# atWork_Main.net
KiCad netlist of a schematic drawn in Altium Designer
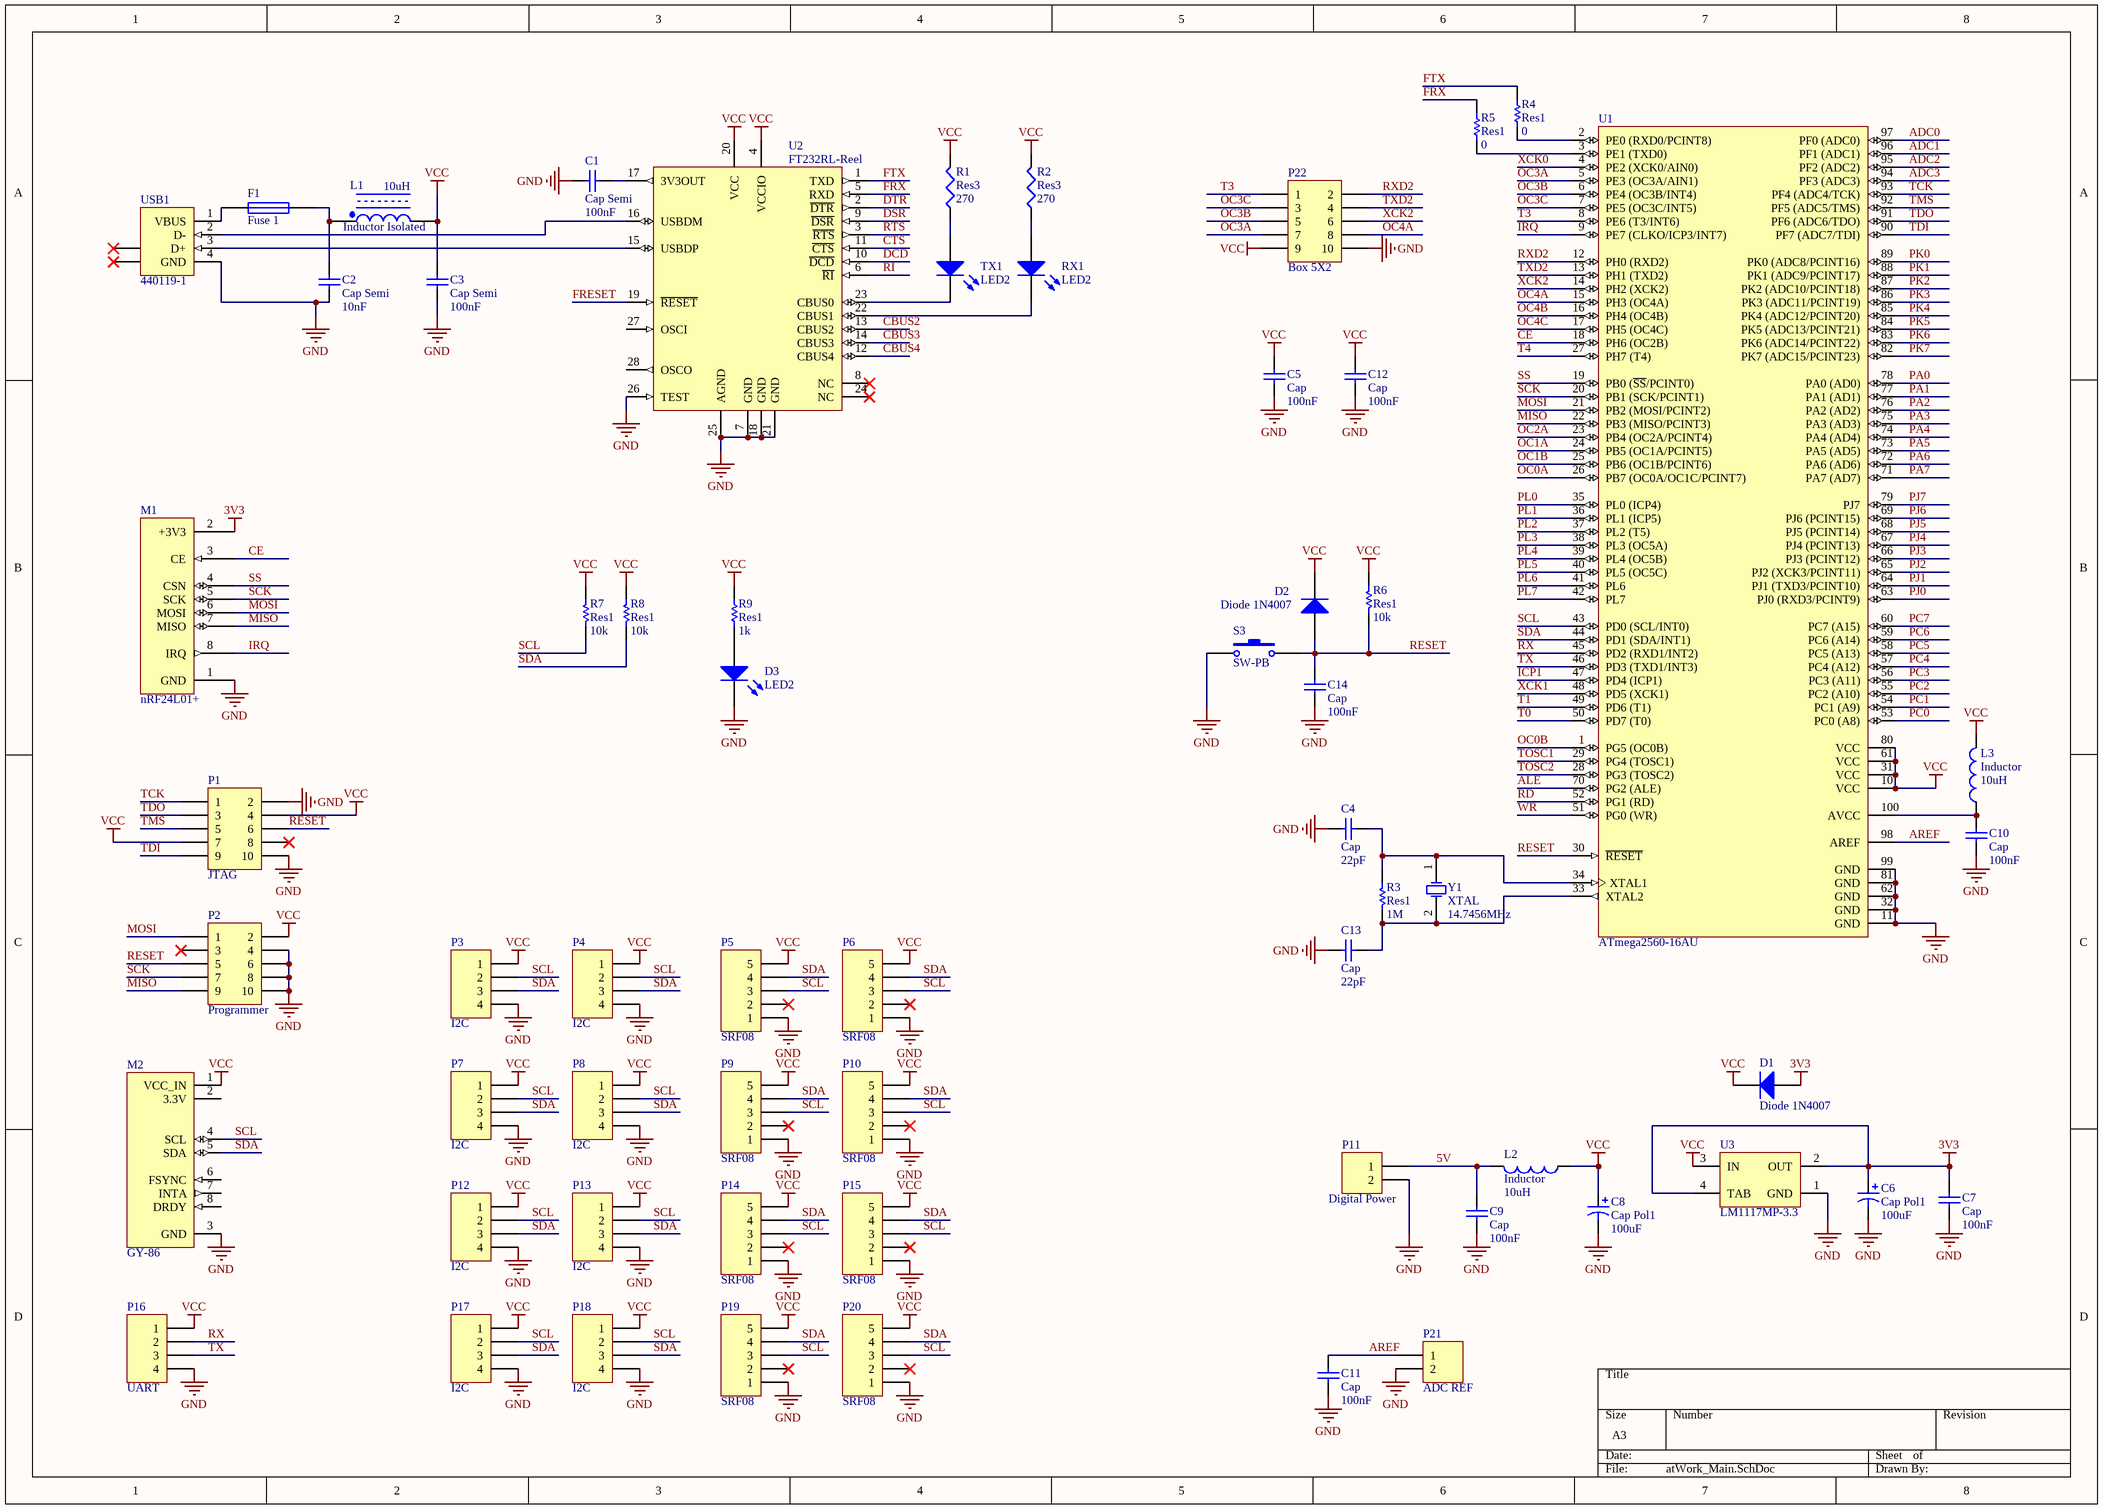
[diagram p0: atWork_Main.SchDoc]

(export (version "E")
  (design (tool "Eeschema 10.0.6"))
  (components
    (comp (ref "C1")
      (value "Cap Semi")
      (footprint "C1206")
      (description "Capacitor (Semiconductor SIM Model)")
      (fields (field (name "ALTIUM_VALUE") "100nF") (field (name "PUBLISHER") "Altium Limited"))
      (libsource (lib "Miscellaneous Devices") (part "Cap Semi"))
    )
    (comp (ref "C2")
      (value "Cap Semi")
      (footprint "C1206")
      (description "Capacitor (Semiconductor SIM Model)")
      (fields (field (name "ALTIUM_VALUE") "10nF") (field (name "PUBLISHER") "Altium Limited"))
      (libsource (lib "Miscellaneous Devices") (part "Cap Semi"))
    )
    (comp (ref "C3")
      (value "Cap Semi")
      (footprint "C1206")
      (description "Capacitor (Semiconductor SIM Model)")
      (fields (field (name "ALTIUM_VALUE") "100nF") (field (name "PUBLISHER") "Altium Limited"))
      (libsource (lib "Miscellaneous Devices") (part "Cap Semi"))
    )
    (comp (ref "C4")
      (value "Cap")
      (footprint "C1206")
      (description "Capacitor")
      (fields (field (name "ALTIUM_VALUE") "22pF") (field (name "PUBLISHER") "Altium Limited"))
      (libsource (lib "Miscellaneous Devices") (part "Cap"))
    )
    (comp (ref "C5")
      (value "Cap")
      (footprint "C1206")
      (description "Capacitor")
      (fields (field (name "ALTIUM_VALUE") "100nF") (field (name "PUBLISHER") "Altium Limited"))
      (libsource (lib "Miscellaneous Devices") (part "Cap"))
    )
    (comp (ref "C6")
      (value "Cap Pol1")
      (footprint "CAP-SMD1")
      (description "Polarized Capacitor (Radial)")
      (fields (field (name "ALTIUM_VALUE") "100uF") (field (name "PUBLISHER") "Altium Limited"))
      (libsource (lib "Miscellaneous Devices") (part "Cap Pol1"))
    )
    (comp (ref "C7")
      (value "Cap")
      (footprint "C1206")
      (description "Capacitor")
      (fields (field (name "ALTIUM_VALUE") "100nF") (field (name "PUBLISHER") "Altium Limited"))
      (libsource (lib "Miscellaneous Devices") (part "Cap"))
    )
    (comp (ref "C8")
      (value "Cap Pol1")
      (footprint "CAP-SMD1")
      (description "Polarized Capacitor (Radial)")
      (fields (field (name "ALTIUM_VALUE") "100uF") (field (name "PUBLISHER") "Altium Limited"))
      (libsource (lib "Miscellaneous Devices") (part "Cap Pol1"))
    )
    (comp (ref "C9")
      (value "Cap")
      (footprint "C1206")
      (description "Capacitor")
      (fields (field (name "ALTIUM_VALUE") "100nF") (field (name "PUBLISHER") "Altium Limited"))
      (libsource (lib "Miscellaneous Devices") (part "Cap"))
    )
    (comp (ref "C10")
      (value "Cap")
      (footprint "C1206")
      (description "Capacitor")
      (fields (field (name "ALTIUM_VALUE") "100nF") (field (name "PUBLISHER") "Altium Limited"))
      (libsource (lib "Miscellaneous Devices") (part "Cap"))
    )
    (comp (ref "C11")
      (value "Cap")
      (footprint "C1206")
      (description "Capacitor")
      (fields (field (name "ALTIUM_VALUE") "100nF") (field (name "PUBLISHER") "Altium Limited"))
      (libsource (lib "Miscellaneous Devices") (part "Cap"))
    )
    (comp (ref "C12")
      (value "Cap")
      (footprint "C1206")
      (description "Capacitor")
      (fields (field (name "ALTIUM_VALUE") "100nF") (field (name "PUBLISHER") "Altium Limited"))
      (libsource (lib "Miscellaneous Devices") (part "Cap"))
    )
    (comp (ref "C13")
      (value "Cap")
      (footprint "C1206")
      (description "Capacitor")
      (fields (field (name "ALTIUM_VALUE") "22pF") (field (name "PUBLISHER") "Altium Limited"))
      (libsource (lib "Miscellaneous Devices") (part "Cap"))
    )
    (comp (ref "C14")
      (value "Cap")
      (footprint "C1206")
      (description "Capacitor")
      (fields (field (name "ALTIUM_VALUE") "100nF") (field (name "PUBLISHER") "Altium Limited"))
      (libsource (lib "Miscellaneous Devices") (part "Cap"))
    )
    (comp (ref "D1")
      (value "Diode 1N4007")
      (footprint "DIODE-SMD")
      (description "1 Amp General Purpose Rectifier")
      (fields (field (name "PUBLISHER") "Altium Limited"))
      (libsource (lib "Miscellaneous Devices") (part "Diode 1N4007"))
    )
    (comp (ref "D2")
      (value "Diode 1N4007")
      (footprint "DIODE-SMD")
      (description "1 Amp General Purpose Rectifier")
      (fields (field (name "PUBLISHER") "Altium Limited"))
      (libsource (lib "Miscellaneous Devices") (part "Diode 1N4007"))
    )
    (comp (ref "D3")
      (value "LED2")
      (footprint "3.2X1.6X1.1")
      (description "Typical RED, GREEN, YELLOW, AMBER GaAs LED")
      (fields (field (name "PUBLISHER") "Altium Limited"))
      (libsource (lib "Miscellaneous Devices") (part "LED2"))
    )
    (comp (ref "F1")
      (value "Fuse 1")
      (footprint "C1206")
      (description "Fuse")
      (fields (field (name "PUBLISHER") "Altium Limited"))
      (libsource (lib "Miscellaneous Devices") (part "Fuse 1"))
    )
    (comp (ref "L1")
      (value "Inductor Isolated")
      (footprint "C1206")
      (description "Isolated Inductor")
      (fields (field (name "ALTIUM_VALUE") "10uH") (field (name "PUBLISHER") "Altium Limited"))
      (libsource (lib "Miscellaneous Devices") (part "Inductor Isolated"))
    )
    (comp (ref "L2")
      (value "Inductor")
      (footprint "C1206")
      (fields (field (name "ALTIUM_VALUE") "10uH") (field (name "PUBLISHER") "Altium Limited"))
      (libsource (lib "") (part "Inductor_1"))
    )
    (comp (ref "L3")
      (value "Inductor")
      (footprint "C1206")
      (fields (field (name "ALTIUM_VALUE") "10uH") (field (name "PUBLISHER") "Altium Limited"))
      (libsource (lib "Miscellaneous Devices") (part "Inductor"))
    )
    (comp (ref "M1")
      (value "nRF24L01+")
      (footprint "NRF24L01+")
      (description "nRF24L01 Single Chip 2.4GHz Tranceiver, +PA +LNA Ver5.1")
      (fields (field (name "DESIGNER") "Meysam Parvizi") (field (name "EMAIL") "meysam.parvizi.ir@gmail.com"))
      (libsource (lib "mp") (part "nRF24L01+"))
    )
    (comp (ref "M2")
      (value "GY-86")
      (footprint "GY-86")
      (description "GY-86 IMU (10DOF MS5611 HMC5883L MPU6050)")
      (fields (field (name "DESIGNER") "Meysam Parvizi") (field (name "EMAIL") "meysam.parvizi.ir@gmail.com"))
      (libsource (lib "mp") (part "GY-86"))
    )
    (comp (ref "P1")
      (value "JTAG")
      (footprint "BOX2X5")
      (description "Box, 5-Pin, Dual row")
      (fields (field (name "DESIGNER") "Meysam Parvizi") (field (name "EMAIL") "meysam.parvizi.ir@gmail.com"))
      (libsource (lib "mp") (part "Box 5X2"))
    )
    (comp (ref "P2")
      (value "Programmer")
      (footprint "BOX2X5")
      (description "Box, 5-Pin, Dual row")
      (fields (field (name "DESIGNER") "Meysam Parvizi") (field (name "EMAIL") "meysam.parvizi.ir@gmail.com"))
      (libsource (lib "mp") (part "Box 5X2"))
    )
    (comp (ref "P3")
      (value "I2C")
      (footprint "XH4PIN")
      (description "Header, 4-Pin")
      (fields (field (name "PUBLISHER") "Altium Limited"))
      (libsource (lib "Miscellaneous Connectors") (part "Header 4"))
    )
    (comp (ref "P4")
      (value "I2C")
      (footprint "XH4PIN")
      (description "Header, 4-Pin")
      (fields (field (name "PUBLISHER") "Altium Limited"))
      (libsource (lib "Miscellaneous Connectors") (part "Header 4"))
    )
    (comp (ref "P5")
      (value "SRF08")
      (footprint "XH5PIN")
      (fields (field (name "PUBLISHER") "Altium Limited"))
      (libsource (lib "Miscellaneous Connectors") (part "Header 5"))
    )
    (comp (ref "P6")
      (value "SRF08")
      (footprint "XH5PIN")
      (fields (field (name "PUBLISHER") "Altium Limited"))
      (libsource (lib "Miscellaneous Connectors") (part "Header 5"))
    )
    (comp (ref "P7")
      (value "I2C")
      (footprint "XH4PIN")
      (description "Header, 4-Pin")
      (fields (field (name "PUBLISHER") "Altium Limited"))
      (libsource (lib "Miscellaneous Connectors") (part "Header 4"))
    )
    (comp (ref "P8")
      (value "I2C")
      (footprint "XH4PIN")
      (description "Header, 4-Pin")
      (fields (field (name "PUBLISHER") "Altium Limited"))
      (libsource (lib "Miscellaneous Connectors") (part "Header 4"))
    )
    (comp (ref "P9")
      (value "SRF08")
      (footprint "XH5PIN")
      (fields (field (name "PUBLISHER") "Altium Limited"))
      (libsource (lib "Miscellaneous Connectors") (part "Header 5"))
    )
    (comp (ref "P10")
      (value "SRF08")
      (footprint "XH5PIN")
      (fields (field (name "PUBLISHER") "Altium Limited"))
      (libsource (lib "Miscellaneous Connectors") (part "Header 5"))
    )
    (comp (ref "P11")
      (value "Digital Power")
      (footprint "XH2PIN")
      (description "Header, 2-Pin")
      (fields (field (name "PUBLISHER") "Altium Limited"))
      (libsource (lib "Miscellaneous Connectors") (part "Header 2"))
    )
    (comp (ref "P12")
      (value "I2C")
      (footprint "XH4PIN")
      (description "Header, 4-Pin")
      (fields (field (name "PUBLISHER") "Altium Limited"))
      (libsource (lib "Miscellaneous Connectors") (part "Header 4"))
    )
    (comp (ref "P13")
      (value "I2C")
      (footprint "XH4PIN")
      (description "Header, 4-Pin")
      (fields (field (name "PUBLISHER") "Altium Limited"))
      (libsource (lib "Miscellaneous Connectors") (part "Header 4"))
    )
    (comp (ref "P14")
      (value "SRF08")
      (footprint "XH5PIN")
      (fields (field (name "PUBLISHER") "Altium Limited"))
      (libsource (lib "Miscellaneous Connectors") (part "Header 5"))
    )
    (comp (ref "P15")
      (value "SRF08")
      (footprint "XH5PIN")
      (fields (field (name "PUBLISHER") "Altium Limited"))
      (libsource (lib "Miscellaneous Connectors") (part "Header 5"))
    )
    (comp (ref "P16")
      (value "UART")
      (footprint "XH4PIN")
      (description "Header, 4-Pin")
      (fields (field (name "PUBLISHER") "Altium Limited"))
      (libsource (lib "Miscellaneous Connectors") (part "Header 4"))
    )
    (comp (ref "P17")
      (value "I2C")
      (footprint "XH4PIN")
      (description "Header, 4-Pin")
      (fields (field (name "PUBLISHER") "Altium Limited"))
      (libsource (lib "Miscellaneous Connectors") (part "Header 4"))
    )
    (comp (ref "P18")
      (value "I2C")
      (footprint "XH4PIN")
      (description "Header, 4-Pin")
      (fields (field (name "PUBLISHER") "Altium Limited"))
      (libsource (lib "Miscellaneous Connectors") (part "Header 4"))
    )
    (comp (ref "P19")
      (value "SRF08")
      (footprint "XH5PIN")
      (fields (field (name "PUBLISHER") "Altium Limited"))
      (libsource (lib "Miscellaneous Connectors") (part "Header 5"))
    )
    (comp (ref "P20")
      (value "SRF08")
      (footprint "XH5PIN")
      (fields (field (name "PUBLISHER") "Altium Limited"))
      (libsource (lib "Miscellaneous Connectors") (part "Header 5"))
    )
    (comp (ref "P21")
      (value "ADC REF")
      (footprint "XH2PIN")
      (description "Header, 2-Pin")
      (fields (field (name "PUBLISHER") "Altium Limited"))
      (libsource (lib "") (part "Header 2_1"))
    )
    (comp (ref "P22")
      (value "Box 5X2")
      (footprint "BOX2X5")
      (description "Box, 5-Pin, Dual row")
      (fields (field (name "DESIGNER") "Meysam Parvizi") (field (name "EMAIL") "meysam.parvizi.ir@gmail.com"))
      (libsource (lib "mp") (part "Box 5X2"))
    )
    (comp (ref "R1")
      (value "Res3")
      (footprint "C1206")
      (description "Resistor")
      (fields (field (name "ALTIUM_VALUE") "270") (field (name "PUBLISHER") "Altium Limited"))
      (libsource (lib "Miscellaneous Devices") (part "Res3"))
    )
    (comp (ref "R2")
      (value "Res3")
      (footprint "C1206")
      (description "Resistor")
      (fields (field (name "ALTIUM_VALUE") "270") (field (name "PUBLISHER") "Altium Limited"))
      (libsource (lib "Miscellaneous Devices") (part "Res3"))
    )
    (comp (ref "R3")
      (value "Res1")
      (footprint "C1206")
      (description "Resistor")
      (fields (field (name "ALTIUM_VALUE") "1M") (field (name "PUBLISHER") "Altium Limited"))
      (libsource (lib "Miscellaneous Devices") (part "Res1"))
    )
    (comp (ref "R4")
      (value "Res1")
      (footprint "C1206")
      (description "Resistor")
      (fields (field (name "ALTIUM_VALUE") "0") (field (name "PUBLISHER") "Altium Limited"))
      (libsource (lib "Miscellaneous Devices") (part "Res1"))
    )
    (comp (ref "R5")
      (value "Res1")
      (footprint "C1206")
      (description "Resistor")
      (fields (field (name "ALTIUM_VALUE") "0") (field (name "PUBLISHER") "Altium Limited"))
      (libsource (lib "Miscellaneous Devices") (part "Res1"))
    )
    (comp (ref "R6")
      (value "Res1")
      (footprint "C1206")
      (description "Resistor")
      (fields (field (name "ALTIUM_VALUE") "10k") (field (name "PUBLISHER") "Altium Limited"))
      (libsource (lib "Miscellaneous Devices") (part "Res1"))
    )
    (comp (ref "R7")
      (value "Res1")
      (footprint "C1206")
      (description "Resistor")
      (fields (field (name "ALTIUM_VALUE") "10k") (field (name "PUBLISHER") "Altium Limited"))
      (libsource (lib "Miscellaneous Devices") (part "Res1"))
    )
    (comp (ref "R8")
      (value "Res1")
      (footprint "C1206")
      (description "Resistor")
      (fields (field (name "ALTIUM_VALUE") "10k") (field (name "PUBLISHER") "Altium Limited"))
      (libsource (lib "Miscellaneous Devices") (part "Res1"))
    )
    (comp (ref "R9")
      (value "Res1")
      (footprint "C1206")
      (description "Resistor")
      (fields (field (name "ALTIUM_VALUE") "1k") (field (name "PUBLISHER") "Altium Limited"))
      (libsource (lib "Miscellaneous Devices") (part "Res1"))
    )
    (comp (ref "RX1")
      (value "LED2")
      (footprint "3.2X1.6X1.1")
      (description "Typical RED, GREEN, YELLOW, AMBER GaAs LED")
      (fields (field (name "PUBLISHER") "Altium Limited"))
      (libsource (lib "Miscellaneous Devices") (part "LED2"))
    )
    (comp (ref "S3")
      (value "SW-PB")
      (footprint "PUSH1")
      (description "Switch")
      (fields (field (name "PUBLISHER") "Altium Limited"))
      (libsource (lib "Miscellaneous Devices") (part "SW-PB"))
    )
    (comp (ref "TX1")
      (value "LED2")
      (footprint "3.2X1.6X1.1")
      (description "Typical RED, GREEN, YELLOW, AMBER GaAs LED")
      (fields (field (name "PUBLISHER") "Altium Limited"))
      (libsource (lib "Miscellaneous Devices") (part "LED2"))
    )
    (comp (ref "U1")
      (value "ATmega2560-16AU")
      (footprint "100A_M")
      (fields (field (name "PUBLISHER") "Altium Limited"))
      (libsource (lib "Atmel Microcontroller 8-Bit megaAVR") (part "ATmega2560-16AU"))
    )
    (comp (ref "U2")
      (value "FT232RL-Reel")
      (footprint "SSOP-28_M")
      (description "USB UART Asynchronous Serial Data Transfer Chip, 28-pin SSOP, Tape and Reel")
      (fields (field (name "MANUFACTURER") "FTDI"))
      (libsource (lib "FTDI FT Series") (part "FT232RL-Reel"))
    )
    (comp (ref "U3")
      (value "LM1117MP-3.3")
      (footprint "MP04A_M")
      (description "800mA Low-Dropout Linear Regulator, 4-pin SOT-223")
      (fields
        (field (name "MANUFACTURER") "National Semiconductor")
        (field (name "PUBLISHER") "Altium Limited")
      )
      (libsource (lib "NSC LDO") (part "LM1117MP-3.3"))
    )
    (comp (ref "USB1")
      (value "440119-1")
      (footprint "mp:USB-B")
      (description "USB 1.1, Right Angle, Thru-Hole, B Type, Receptacle, 4 Position, Beige")
      (fields (field (name "PUBLISHER") "Altium Limited"))
      (libsource (lib "AMP Serial Bus USB") (part "440119-1"))
    )
    (comp (ref "Y1")
      (value "XTAL")
      (footprint "XTAL")
      (description "Crystal Oscillator")
      (fields
        (field (name "ALTIUM_VALUE") "14.7456MHz")
        (field (name "DESIGNER") "Meysam Parvizi")
        (field (name "EMAIL") "meysam.parvizi.ir@gmail.com")
      )
      (libsource (lib "mp") (part "XTAL"))
    )
  )
  (nets
    (net (code "1") (name "/5V") (class "Default")
      (node (ref "C9") (pin "2") (pinfunction "2_2") (pintype "passive"))
      (node (ref "L2") (pin "1") (pinfunction "1_1") (pintype "passive"))
      (node (ref "P11") (pin "1") (pinfunction "1_1") (pintype "passive"))
    )
    (net (code "2") (name "/ADC0") (class "Default")
      (node (ref "U1") (pin "97") (pinfunction "PF0_(ADC0)_97") (pintype "bidirectional"))
    )
    (net (code "3") (name "/ADC1") (class "Default")
      (node (ref "U1") (pin "96") (pinfunction "PF1_(ADC1)_96") (pintype "bidirectional"))
    )
    (net (code "4") (name "/ADC2") (class "Default")
      (node (ref "U1") (pin "95") (pinfunction "PF2_(ADC2)_95") (pintype "bidirectional"))
    )
    (net (code "5") (name "/ADC3") (class "Default")
      (node (ref "U1") (pin "94") (pinfunction "PF3_(ADC3)_94") (pintype "bidirectional"))
    )
    (net (code "6") (name "/ALE") (class "Default")
      (node (ref "U1") (pin "70") (pinfunction "PG2_(ALE)_70") (pintype "bidirectional"))
    )
    (net (code "7") (name "/AREF") (class "Default")
      (node (ref "C11") (pin "2") (pinfunction "2_2") (pintype "passive"))
      (node (ref "P21") (pin "1") (pinfunction "1_1") (pintype "passive"))
      (node (ref "U1") (pin "98") (pinfunction "AREF_98") (pintype "power_in"))
    )
    (net (code "8") (name "/CBUS2") (class "Default")
      (node (ref "U2") (pin "13") (pinfunction "CBUS2_13") (pintype "bidirectional"))
    )
    (net (code "9") (name "/CBUS3") (class "Default")
      (node (ref "U2") (pin "14") (pinfunction "CBUS3_14") (pintype "bidirectional"))
    )
    (net (code "10") (name "/CBUS4") (class "Default")
      (node (ref "U2") (pin "12") (pinfunction "CBUS4_12") (pintype "bidirectional"))
    )
    (net (code "11") (name "/CE") (class "Default")
      (node (ref "M1") (pin "3") (pinfunction "CE_3") (pintype "input"))
      (node (ref "U1") (pin "18") (pinfunction "PH6_(OC2B)_18") (pintype "bidirectional"))
    )
    (net (code "12") (name "/CTS") (class "Default")
      (node (ref "U2") (pin "11") (pinfunction "~{CTS}_11") (pintype "input"))
    )
    (net (code "13") (name "/DCD") (class "Default")
      (node (ref "U2") (pin "10") (pinfunction "~{DCD}_10") (pintype "input"))
    )
    (net (code "14") (name "/DSR") (class "Default")
      (node (ref "U2") (pin "9") (pinfunction "~{DSR}_9") (pintype "input"))
    )
    (net (code "15") (name "/DTR") (class "Default")
      (node (ref "U2") (pin "2") (pinfunction "~{DTR}_2") (pintype "output"))
    )
    (net (code "16") (name "/FRESET") (class "Default")
      (node (ref "U2") (pin "19") (pinfunction "~{RESET}_19") (pintype "input"))
    )
    (net (code "17") (name "/FRX") (class "Default")
      (node (ref "R5") (pin "2") (pinfunction "2_2") (pintype "passive"))
      (node (ref "U2") (pin "5") (pinfunction "RXD_5") (pintype "input"))
    )
    (net (code "18") (name "/FTX") (class "Default")
      (node (ref "R4") (pin "1") (pinfunction "1_1") (pintype "passive"))
      (node (ref "U2") (pin "1") (pinfunction "TXD_1") (pintype "output"))
    )
    (net (code "19") (name "/ICP1") (class "Default")
      (node (ref "U1") (pin "47") (pinfunction "PD4_(ICP1)_47") (pintype "bidirectional"))
    )
    (net (code "20") (name "/IRQ") (class "Default")
      (node (ref "M1") (pin "8") (pinfunction "IRQ_8") (pintype "output"))
      (node (ref "U1") (pin "9") (pinfunction "PE7_(CLKO/ICP3/INT7)_9") (pintype "bidirectional"))
    )
    (net (code "21") (name "/MISO") (class "Default")
      (node (ref "M1") (pin "7") (pinfunction "MISO_7") (pintype "bidirectional"))
      (node (ref "P2") (pin "9") (pinfunction "9_9") (pintype "passive"))
      (node (ref "U1") (pin "22") (pinfunction "PB3_(MISO/PCINT3)_22") (pintype "bidirectional"))
    )
    (net (code "22") (name "/MOSI") (class "Default")
      (node (ref "M1") (pin "6") (pinfunction "MOSI_6") (pintype "bidirectional"))
      (node (ref "P2") (pin "1") (pinfunction "1_1") (pintype "passive"))
      (node (ref "U1") (pin "21") (pinfunction "PB2_(MOSI/PCINT2)_21") (pintype "bidirectional"))
    )
    (net (code "23") (name "/OC0A") (class "Default")
      (node (ref "U1") (pin "26") (pinfunction "PB7_(OC0A/OC1C/PCINT7)_26") (pintype "bidirectional"))
    )
    (net (code "24") (name "/OC0B") (class "Default")
      (node (ref "U1") (pin "1") (pinfunction "PG5_(OC0B)_1") (pintype "bidirectional"))
    )
    (net (code "25") (name "/OC1A") (class "Default")
      (node (ref "U1") (pin "24") (pinfunction "PB5_(OC1A/PCINT5)_24") (pintype "bidirectional"))
    )
    (net (code "26") (name "/OC1B") (class "Default")
      (node (ref "U1") (pin "25") (pinfunction "PB6_(OC1B/PCINT6)_25") (pintype "bidirectional"))
    )
    (net (code "27") (name "/OC2A") (class "Default")
      (node (ref "U1") (pin "23") (pinfunction "PB4_(OC2A/PCINT4)_23") (pintype "bidirectional"))
    )
    (net (code "28") (name "/OC3A") (class "Default")
      (node (ref "P22") (pin "7") (pinfunction "7_7") (pintype "passive"))
      (node (ref "U1") (pin "5") (pinfunction "PE3_(OC3A/AIN1)_5") (pintype "bidirectional"))
    )
    (net (code "29") (name "/OC3B") (class "Default")
      (node (ref "P22") (pin "5") (pinfunction "5_5") (pintype "passive"))
      (node (ref "U1") (pin "6") (pinfunction "PE4_(OC3B/INT4)_6") (pintype "bidirectional"))
    )
    (net (code "30") (name "/OC3C") (class "Default")
      (node (ref "P22") (pin "3") (pinfunction "3_3") (pintype "passive"))
      (node (ref "U1") (pin "7") (pinfunction "PE5_(OC3C/INT5)_7") (pintype "bidirectional"))
    )
    (net (code "31") (name "/OC4A") (class "Default")
      (node (ref "P22") (pin "8") (pinfunction "8_8") (pintype "passive"))
      (node (ref "U1") (pin "15") (pinfunction "PH3_(OC4A)_15") (pintype "bidirectional"))
    )
    (net (code "32") (name "/OC4B") (class "Default")
      (node (ref "U1") (pin "16") (pinfunction "PH4_(OC4B)_16") (pintype "bidirectional"))
    )
    (net (code "33") (name "/OC4C") (class "Default")
      (node (ref "U1") (pin "17") (pinfunction "PH5_(OC4C)_17") (pintype "bidirectional"))
    )
    (net (code "34") (name "/PA0") (class "Default")
      (node (ref "U1") (pin "78") (pinfunction "PA0_(AD0)_78") (pintype "bidirectional"))
    )
    (net (code "35") (name "/PA1") (class "Default")
      (node (ref "U1") (pin "77") (pinfunction "PA1_(AD1)_77") (pintype "bidirectional"))
    )
    (net (code "36") (name "/PA2") (class "Default")
      (node (ref "U1") (pin "76") (pinfunction "PA2_(AD2)_76") (pintype "bidirectional"))
    )
    (net (code "37") (name "/PA3") (class "Default")
      (node (ref "U1") (pin "75") (pinfunction "PA3_(AD3)_75") (pintype "bidirectional"))
    )
    (net (code "38") (name "/PA4") (class "Default")
      (node (ref "U1") (pin "74") (pinfunction "PA4_(AD4)_74") (pintype "bidirectional"))
    )
    (net (code "39") (name "/PA5") (class "Default")
      (node (ref "U1") (pin "73") (pinfunction "PA5_(AD5)_73") (pintype "bidirectional"))
    )
    (net (code "40") (name "/PA6") (class "Default")
      (node (ref "U1") (pin "72") (pinfunction "PA6_(AD6)_72") (pintype "bidirectional"))
    )
    (net (code "41") (name "/PA7") (class "Default")
      (node (ref "U1") (pin "71") (pinfunction "PA7_(AD7)_71") (pintype "bidirectional"))
    )
    (net (code "42") (name "/PC0") (class "Default")
      (node (ref "U1") (pin "53") (pinfunction "PC0_(A8)_53") (pintype "bidirectional"))
    )
    (net (code "43") (name "/PC1") (class "Default")
      (node (ref "U1") (pin "54") (pinfunction "PC1_(A9)_54") (pintype "bidirectional"))
    )
    (net (code "44") (name "/PC2") (class "Default")
      (node (ref "U1") (pin "55") (pinfunction "PC2_(A10)_55") (pintype "bidirectional"))
    )
    (net (code "45") (name "/PC3") (class "Default")
      (node (ref "U1") (pin "56") (pinfunction "PC3_(A11)_56") (pintype "bidirectional"))
    )
    (net (code "46") (name "/PC4") (class "Default")
      (node (ref "U1") (pin "57") (pinfunction "PC4_(A12)_57") (pintype "bidirectional"))
    )
    (net (code "47") (name "/PC5") (class "Default")
      (node (ref "U1") (pin "58") (pinfunction "PC5_(A13)_58") (pintype "bidirectional"))
    )
    (net (code "48") (name "/PC6") (class "Default")
      (node (ref "U1") (pin "59") (pinfunction "PC6_(A14)_59") (pintype "bidirectional"))
    )
    (net (code "49") (name "/PC7") (class "Default")
      (node (ref "U1") (pin "60") (pinfunction "PC7_(A15)_60") (pintype "bidirectional"))
    )
    (net (code "50") (name "/PJ0") (class "Default")
      (node (ref "U1") (pin "63") (pinfunction "PJ0_(RXD3/PCINT9)_63") (pintype "bidirectional"))
    )
    (net (code "51") (name "/PJ1") (class "Default")
      (node (ref "U1") (pin "64") (pinfunction "PJ1_(TXD3/PCINT10)_64") (pintype "bidirectional"))
    )
    (net (code "52") (name "/PJ2") (class "Default")
      (node (ref "U1") (pin "65") (pinfunction "PJ2_(XCK3/PCINT11)_65") (pintype "bidirectional"))
    )
    (net (code "53") (name "/PJ3") (class "Default")
      (node (ref "U1") (pin "66") (pinfunction "PJ3_(PCINT12)_66") (pintype "bidirectional"))
    )
    (net (code "54") (name "/PJ4") (class "Default")
      (node (ref "U1") (pin "67") (pinfunction "PJ4_(PCINT13)_67") (pintype "bidirectional"))
    )
    (net (code "55") (name "/PJ5") (class "Default")
      (node (ref "U1") (pin "68") (pinfunction "PJ5_(PCINT14)_68") (pintype "bidirectional"))
    )
    (net (code "56") (name "/PJ6") (class "Default")
      (node (ref "U1") (pin "69") (pinfunction "PJ6_(PCINT15)_69") (pintype "bidirectional"))
    )
    (net (code "57") (name "/PJ7") (class "Default")
      (node (ref "U1") (pin "79") (pinfunction "PJ7_79") (pintype "bidirectional"))
    )
    (net (code "58") (name "/PK0") (class "Default")
      (node (ref "U1") (pin "89") (pinfunction "PK0_(ADC8/PCINT16)_89") (pintype "bidirectional"))
    )
    (net (code "59") (name "/PK1") (class "Default")
      (node (ref "U1") (pin "88") (pinfunction "PK1_(ADC9/PCINT17)_88") (pintype "bidirectional"))
    )
    (net (code "60") (name "/PK2") (class "Default")
      (node (ref "U1") (pin "87") (pinfunction "PK2_(ADC10/PCINT18)_87") (pintype "bidirectional"))
    )
    (net (code "61") (name "/PK3") (class "Default")
      (node (ref "U1") (pin "86") (pinfunction "PK3_(ADC11/PCINT19)_86") (pintype "bidirectional"))
    )
    (net (code "62") (name "/PK4") (class "Default")
      (node (ref "U1") (pin "85") (pinfunction "PK4_(ADC12/PCINT20)_85") (pintype "bidirectional"))
    )
    (net (code "63") (name "/PK5") (class "Default")
      (node (ref "U1") (pin "84") (pinfunction "PK5_(ADC13/PCINT21)_84") (pintype "bidirectional"))
    )
    (net (code "64") (name "/PK6") (class "Default")
      (node (ref "U1") (pin "83") (pinfunction "PK6_(ADC14/PCINT22)_83") (pintype "bidirectional"))
    )
    (net (code "65") (name "/PK7") (class "Default")
      (node (ref "U1") (pin "82") (pinfunction "PK7_(ADC15/PCINT23)_82") (pintype "bidirectional"))
    )
    (net (code "66") (name "/PL0") (class "Default")
      (node (ref "U1") (pin "35") (pinfunction "PL0_(ICP4)_35") (pintype "bidirectional"))
    )
    (net (code "67") (name "/PL1") (class "Default")
      (node (ref "U1") (pin "36") (pinfunction "PL1_(ICP5)_36") (pintype "bidirectional"))
    )
    (net (code "68") (name "/PL2") (class "Default")
      (node (ref "U1") (pin "37") (pinfunction "PL2_(T5)_37") (pintype "bidirectional"))
    )
    (net (code "69") (name "/PL3") (class "Default")
      (node (ref "U1") (pin "38") (pinfunction "PL3_(OC5A)_38") (pintype "bidirectional"))
    )
    (net (code "70") (name "/PL4") (class "Default")
      (node (ref "U1") (pin "39") (pinfunction "PL4_(OC5B)_39") (pintype "bidirectional"))
    )
    (net (code "71") (name "/PL5") (class "Default")
      (node (ref "U1") (pin "40") (pinfunction "PL5_(OC5C)_40") (pintype "bidirectional"))
    )
    (net (code "72") (name "/PL6") (class "Default")
      (node (ref "U1") (pin "41") (pinfunction "PL6_41") (pintype "bidirectional"))
    )
    (net (code "73") (name "/PL7") (class "Default")
      (node (ref "U1") (pin "42") (pinfunction "PL7_42") (pintype "bidirectional"))
    )
    (net (code "74") (name "/RD") (class "Default")
      (node (ref "U1") (pin "52") (pinfunction "PG1_(RD)_52") (pintype "bidirectional"))
    )
    (net (code "75") (name "/RESET") (class "Default")
      (node (ref "C14") (pin "2") (pinfunction "2_2") (pintype "passive"))
      (node (ref "D2") (pin "1") (pinfunction "A_1") (pintype "passive"))
      (node (ref "P1") (pin "6") (pinfunction "6_6") (pintype "passive"))
      (node (ref "P2") (pin "5") (pinfunction "5_5") (pintype "passive"))
      (node (ref "R6") (pin "2") (pinfunction "2_2") (pintype "passive"))
      (node (ref "S3") (pin "1") (pinfunction "1_1") (pintype "passive"))
      (node (ref "U1") (pin "30") (pinfunction "~{RESET}_30") (pintype "input"))
    )
    (net (code "76") (name "/RI") (class "Default")
      (node (ref "U2") (pin "6") (pinfunction "~{RI}_6") (pintype "input"))
    )
    (net (code "77") (name "/RTS") (class "Default")
      (node (ref "U2") (pin "3") (pinfunction "~{RTS}_3") (pintype "output"))
    )
    (net (code "78") (name "/RX") (class "Default")
      (node (ref "P16") (pin "2") (pinfunction "2_2") (pintype "passive"))
      (node (ref "U1") (pin "45") (pinfunction "PD2_(RXD1/INT2)_45") (pintype "bidirectional"))
    )
    (net (code "79") (name "/RXD2") (class "Default")
      (node (ref "P22") (pin "2") (pinfunction "2_2") (pintype "passive"))
      (node (ref "U1") (pin "12") (pinfunction "PH0_(RXD2)_12") (pintype "bidirectional"))
    )
    (net (code "80") (name "/SCK") (class "Default")
      (node (ref "M1") (pin "5") (pinfunction "SCK_5") (pintype "bidirectional"))
      (node (ref "P2") (pin "7") (pinfunction "7_7") (pintype "passive"))
      (node (ref "U1") (pin "20") (pinfunction "PB1_(SCK/PCINT1)_20") (pintype "bidirectional"))
    )
    (net (code "81") (name "/SCL") (class "Default")
      (node (ref "M2") (pin "4") (pinfunction "SCL_4") (pintype "bidirectional"))
      (node (ref "P10") (pin "3") (pinfunction "3_3") (pintype "passive"))
      (node (ref "P12") (pin "2") (pinfunction "2_2") (pintype "passive"))
      (node (ref "P13") (pin "2") (pinfunction "2_2") (pintype "passive"))
      (node (ref "P14") (pin "3") (pinfunction "3_3") (pintype "passive"))
      (node (ref "P15") (pin "3") (pinfunction "3_3") (pintype "passive"))
      (node (ref "P17") (pin "2") (pinfunction "2_2") (pintype "passive"))
      (node (ref "P18") (pin "2") (pinfunction "2_2") (pintype "passive"))
      (node (ref "P19") (pin "3") (pinfunction "3_3") (pintype "passive"))
      (node (ref "P20") (pin "3") (pinfunction "3_3") (pintype "passive"))
      (node (ref "P3") (pin "2") (pinfunction "2_2") (pintype "passive"))
      (node (ref "P4") (pin "2") (pinfunction "2_2") (pintype "passive"))
      (node (ref "P5") (pin "3") (pinfunction "3_3") (pintype "passive"))
      (node (ref "P6") (pin "3") (pinfunction "3_3") (pintype "passive"))
      (node (ref "P7") (pin "2") (pinfunction "2_2") (pintype "passive"))
      (node (ref "P8") (pin "2") (pinfunction "2_2") (pintype "passive"))
      (node (ref "P9") (pin "3") (pinfunction "3_3") (pintype "passive"))
      (node (ref "R7") (pin "2") (pinfunction "2_2") (pintype "passive"))
      (node (ref "U1") (pin "43") (pinfunction "PD0_(SCL/INT0)_43") (pintype "bidirectional"))
    )
    (net (code "82") (name "/SDA") (class "Default")
      (node (ref "M2") (pin "5") (pinfunction "SDA_5") (pintype "bidirectional"))
      (node (ref "P10") (pin "4") (pinfunction "4_4") (pintype "passive"))
      (node (ref "P12") (pin "3") (pinfunction "3_3") (pintype "passive"))
      (node (ref "P13") (pin "3") (pinfunction "3_3") (pintype "passive"))
      (node (ref "P14") (pin "4") (pinfunction "4_4") (pintype "passive"))
      (node (ref "P15") (pin "4") (pinfunction "4_4") (pintype "passive"))
      (node (ref "P17") (pin "3") (pinfunction "3_3") (pintype "passive"))
      (node (ref "P18") (pin "3") (pinfunction "3_3") (pintype "passive"))
      (node (ref "P19") (pin "4") (pinfunction "4_4") (pintype "passive"))
      (node (ref "P20") (pin "4") (pinfunction "4_4") (pintype "passive"))
      (node (ref "P3") (pin "3") (pinfunction "3_3") (pintype "passive"))
      (node (ref "P4") (pin "3") (pinfunction "3_3") (pintype "passive"))
      (node (ref "P5") (pin "4") (pinfunction "4_4") (pintype "passive"))
      (node (ref "P6") (pin "4") (pinfunction "4_4") (pintype "passive"))
      (node (ref "P7") (pin "3") (pinfunction "3_3") (pintype "passive"))
      (node (ref "P8") (pin "3") (pinfunction "3_3") (pintype "passive"))
      (node (ref "P9") (pin "4") (pinfunction "4_4") (pintype "passive"))
      (node (ref "R8") (pin "2") (pinfunction "2_2") (pintype "passive"))
      (node (ref "U1") (pin "44") (pinfunction "PD1_(SDA/INT1)_44") (pintype "bidirectional"))
    )
    (net (code "83") (name "/SS") (class "Default")
      (node (ref "M1") (pin "4") (pinfunction "CSN_4") (pintype "bidirectional"))
      (node (ref "U1") (pin "19") (pinfunction "PB0_(~{SS}/PCINT0)_19") (pintype "bidirectional"))
    )
    (net (code "84") (name "/T0") (class "Default")
      (node (ref "U1") (pin "50") (pinfunction "PD7_(T0)_50") (pintype "bidirectional"))
    )
    (net (code "85") (name "/T1") (class "Default")
      (node (ref "U1") (pin "49") (pinfunction "PD6_(T1)_49") (pintype "bidirectional"))
    )
    (net (code "86") (name "/T3") (class "Default")
      (node (ref "P22") (pin "1") (pinfunction "1_1") (pintype "passive"))
      (node (ref "U1") (pin "8") (pinfunction "PE6_(T3/INT6)_8") (pintype "bidirectional"))
    )
    (net (code "87") (name "/T4") (class "Default")
      (node (ref "U1") (pin "27") (pinfunction "PH7_(T4)_27") (pintype "bidirectional"))
    )
    (net (code "88") (name "/TCK") (class "Default")
      (node (ref "P1") (pin "1") (pinfunction "1_1") (pintype "passive"))
      (node (ref "U1") (pin "93") (pinfunction "PF4_(ADC4/TCK)_93") (pintype "bidirectional"))
    )
    (net (code "89") (name "/TDI") (class "Default")
      (node (ref "P1") (pin "9") (pinfunction "9_9") (pintype "passive"))
      (node (ref "U1") (pin "90") (pinfunction "PF7_(ADC7/TDI)_90") (pintype "bidirectional"))
    )
    (net (code "90") (name "/TDO") (class "Default")
      (node (ref "P1") (pin "3") (pinfunction "3_3") (pintype "passive"))
      (node (ref "U1") (pin "91") (pinfunction "PF6_(ADC6/TDO)_91") (pintype "bidirectional"))
    )
    (net (code "91") (name "/TMS") (class "Default")
      (node (ref "P1") (pin "5") (pinfunction "5_5") (pintype "passive"))
      (node (ref "U1") (pin "92") (pinfunction "PF5_(ADC5/TMS)_92") (pintype "bidirectional"))
    )
    (net (code "92") (name "/TOSC1") (class "Default")
      (node (ref "U1") (pin "29") (pinfunction "PG4_(TOSC1)_29") (pintype "bidirectional"))
    )
    (net (code "93") (name "/TOSC2") (class "Default")
      (node (ref "U1") (pin "28") (pinfunction "PG3_(TOSC2)_28") (pintype "bidirectional"))
    )
    (net (code "94") (name "/TX") (class "Default")
      (node (ref "P16") (pin "3") (pinfunction "3_3") (pintype "passive"))
      (node (ref "U1") (pin "46") (pinfunction "PD3_(TXD1/INT3)_46") (pintype "bidirectional"))
    )
    (net (code "95") (name "/TXD2") (class "Default")
      (node (ref "P22") (pin "4") (pinfunction "4_4") (pintype "passive"))
      (node (ref "U1") (pin "13") (pinfunction "PH1_(TXD2)_13") (pintype "bidirectional"))
    )
    (net (code "96") (name "/WR") (class "Default")
      (node (ref "U1") (pin "51") (pinfunction "PG0_(WR)_51") (pintype "bidirectional"))
    )
    (net (code "97") (name "/XCK0") (class "Default")
      (node (ref "U1") (pin "4") (pinfunction "PE2_(XCK0/AIN0)_4") (pintype "bidirectional"))
    )
    (net (code "98") (name "/XCK1") (class "Default")
      (node (ref "U1") (pin "48") (pinfunction "PD5_(XCK1)_48") (pintype "bidirectional"))
    )
    (net (code "99") (name "/XCK2") (class "Default")
      (node (ref "P22") (pin "6") (pinfunction "6_6") (pintype "passive"))
      (node (ref "U1") (pin "14") (pinfunction "PH2_(XCK2)_14") (pintype "bidirectional"))
    )
    (net (code "100") (name "3V3") (class "Default")
      (node (ref "C6") (pin "1") (pinfunction "1_1") (pintype "passive"))
      (node (ref "C7") (pin "2") (pinfunction "2_2") (pintype "passive"))
      (node (ref "D1") (pin "1") (pinfunction "A_1") (pintype "passive"))
      (node (ref "M1") (pin "2") (pinfunction "+3V3_2") (pintype "power_in"))
      (node (ref "U3") (pin "2") (pinfunction "OUT_2") (pintype "power_in"))
      (node (ref "U3") (pin "4") (pinfunction "TAB_4") (pintype "power_in"))
    )
    (net (code "101") (name "GND") (class "Default")
      (node (ref "C1") (pin "2") (pinfunction "2_2") (pintype "passive"))
      (node (ref "C10") (pin "1") (pinfunction "1_1") (pintype "passive"))
      (node (ref "C11") (pin "1") (pinfunction "1_1") (pintype "passive"))
      (node (ref "C12") (pin "1") (pinfunction "1_1") (pintype "passive"))
      (node (ref "C13") (pin "1") (pinfunction "1_1") (pintype "passive"))
      (node (ref "C14") (pin "1") (pinfunction "1_1") (pintype "passive"))
      (node (ref "C2") (pin "1") (pinfunction "1_1") (pintype "passive"))
      (node (ref "C3") (pin "1") (pinfunction "1_1") (pintype "passive"))
      (node (ref "C4") (pin "1") (pinfunction "1_1") (pintype "passive"))
      (node (ref "C5") (pin "1") (pinfunction "1_1") (pintype "passive"))
      (node (ref "C6") (pin "2") (pinfunction "2_2") (pintype "passive"))
      (node (ref "C7") (pin "1") (pinfunction "1_1") (pintype "passive"))
      (node (ref "C8") (pin "2") (pinfunction "2_2") (pintype "passive"))
      (node (ref "C9") (pin "1") (pinfunction "1_1") (pintype "passive"))
      (node (ref "D3") (pin "2") (pinfunction "K_2") (pintype "passive"))
      (node (ref "M1") (pin "1") (pinfunction "GND_1") (pintype "power_in"))
      (node (ref "M2") (pin "3") (pinfunction "GND_3") (pintype "power_in"))
      (node (ref "P1") (pin "10") (pinfunction "10_10") (pintype "passive"))
      (node (ref "P1") (pin "2") (pinfunction "2_2") (pintype "passive"))
      (node (ref "P10") (pin "1") (pinfunction "1_1") (pintype "passive"))
      (node (ref "P11") (pin "2") (pinfunction "2_2") (pintype "passive"))
      (node (ref "P12") (pin "4") (pinfunction "4_4") (pintype "passive"))
      (node (ref "P13") (pin "4") (pinfunction "4_4") (pintype "passive"))
      (node (ref "P14") (pin "1") (pinfunction "1_1") (pintype "passive"))
      (node (ref "P15") (pin "1") (pinfunction "1_1") (pintype "passive"))
      (node (ref "P16") (pin "4") (pinfunction "4_4") (pintype "passive"))
      (node (ref "P17") (pin "4") (pinfunction "4_4") (pintype "passive"))
      (node (ref "P18") (pin "4") (pinfunction "4_4") (pintype "passive"))
      (node (ref "P19") (pin "1") (pinfunction "1_1") (pintype "passive"))
      (node (ref "P2") (pin "10") (pinfunction "10_10") (pintype "passive"))
      (node (ref "P2") (pin "4") (pinfunction "4_4") (pintype "passive"))
      (node (ref "P2") (pin "6") (pinfunction "6_6") (pintype "passive"))
      (node (ref "P2") (pin "8") (pinfunction "8_8") (pintype "passive"))
      (node (ref "P20") (pin "1") (pinfunction "1_1") (pintype "passive"))
      (node (ref "P21") (pin "2") (pinfunction "2_2") (pintype "passive"))
      (node (ref "P22") (pin "10") (pinfunction "10_10") (pintype "passive"))
      (node (ref "P3") (pin "4") (pinfunction "4_4") (pintype "passive"))
      (node (ref "P4") (pin "4") (pinfunction "4_4") (pintype "passive"))
      (node (ref "P5") (pin "1") (pinfunction "1_1") (pintype "passive"))
      (node (ref "P6") (pin "1") (pinfunction "1_1") (pintype "passive"))
      (node (ref "P7") (pin "4") (pinfunction "4_4") (pintype "passive"))
      (node (ref "P8") (pin "4") (pinfunction "4_4") (pintype "passive"))
      (node (ref "P9") (pin "1") (pinfunction "1_1") (pintype "passive"))
      (node (ref "S3") (pin "2") (pinfunction "2_2") (pintype "passive"))
      (node (ref "U1") (pin "11") (pinfunction "GND_11") (pintype "power_in"))
      (node (ref "U1") (pin "32") (pinfunction "GND_32") (pintype "power_in"))
      (node (ref "U1") (pin "62") (pinfunction "GND_62") (pintype "power_in"))
      (node (ref "U1") (pin "81") (pinfunction "GND_81") (pintype "power_in"))
      (node (ref "U1") (pin "99") (pinfunction "GND_99") (pintype "power_in"))
      (node (ref "U2") (pin "18") (pinfunction "GND_18") (pintype "power_in"))
      (node (ref "U2") (pin "21") (pinfunction "GND_21") (pintype "power_in"))
      (node (ref "U2") (pin "25") (pinfunction "AGND_25") (pintype "power_in"))
      (node (ref "U2") (pin "26") (pinfunction "TEST_26") (pintype "input"))
      (node (ref "U2") (pin "7") (pinfunction "GND_7") (pintype "power_in"))
      (node (ref "U3") (pin "1") (pinfunction "GND_1") (pintype "power_in"))
      (node (ref "USB1") (pin "4") (pinfunction "GND_4") (pintype "power_in"))
    )
    (net (code "102") (name "Net-(C2-Pad2)") (class "Default")
      (node (ref "C2") (pin "2") (pinfunction "2_2") (pintype "passive"))
      (node (ref "F1") (pin "2") (pinfunction "2_2") (pintype "passive"))
      (node (ref "L1") (pin "1") (pinfunction "1_1") (pintype "passive"))
    )
    (net (code "103") (name "Net-(D3-A)") (class "Default")
      (node (ref "D3") (pin "1") (pinfunction "A_1") (pintype "passive"))
      (node (ref "R9") (pin "1") (pinfunction "1_1") (pintype "passive"))
    )
    (net (code "104") (name "Net-(RX1-A)") (class "Default")
      (node (ref "R2") (pin "1") (pinfunction "1_1") (pintype "passive"))
      (node (ref "RX1") (pin "1") (pinfunction "A_1") (pintype "passive"))
    )
    (net (code "105") (name "Net-(RX1-K)") (class "Default")
      (node (ref "RX1") (pin "2") (pinfunction "K_2") (pintype "passive"))
      (node (ref "U2") (pin "22") (pinfunction "CBUS1_22") (pintype "bidirectional"))
    )
    (net (code "106") (name "Net-(TX1-A)") (class "Default")
      (node (ref "R1") (pin "1") (pinfunction "1_1") (pintype "passive"))
      (node (ref "TX1") (pin "1") (pinfunction "A_1") (pintype "passive"))
    )
    (net (code "107") (name "Net-(TX1-K)") (class "Default")
      (node (ref "TX1") (pin "2") (pinfunction "K_2") (pintype "passive"))
      (node (ref "U2") (pin "23") (pinfunction "CBUS0_23") (pintype "bidirectional"))
    )
    (net (code "108") (name "Net-(U1-AVCC)") (class "Default")
      (node (ref "C10") (pin "2") (pinfunction "2_2") (pintype "passive"))
      (node (ref "L3") (pin "1") (pinfunction "1_1") (pintype "passive"))
      (node (ref "U1") (pin "100") (pinfunction "AVCC_100") (pintype "power_in"))
    )
    (net (code "109") (name "Net-(U1-PE0_(RXD0{slash}PCINT8))") (class "Default")
      (node (ref "R4") (pin "2") (pinfunction "2_2") (pintype "passive"))
      (node (ref "U1") (pin "2") (pinfunction "PE0_(RXD0/PCINT8)_2") (pintype "bidirectional"))
    )
    (net (code "110") (name "Net-(U1-PE1_(TXD0))") (class "Default")
      (node (ref "R5") (pin "1") (pinfunction "1_1") (pintype "passive"))
      (node (ref "U1") (pin "3") (pinfunction "PE1_(TXD0)_3") (pintype "bidirectional"))
    )
    (net (code "111") (name "Net-(U1-XTAL1)") (class "Default")
      (node (ref "C4") (pin "2") (pinfunction "2_2") (pintype "passive"))
      (node (ref "R3") (pin "1") (pinfunction "1_1") (pintype "passive"))
      (node (ref "U1") (pin "34") (pinfunction "XTAL1_34") (pintype "input"))
      (node (ref "Y1") (pin "1") (pinfunction "OSC1_1") (pintype "passive"))
    )
    (net (code "112") (name "Net-(U1-XTAL2)") (class "Default")
      (node (ref "C13") (pin "2") (pinfunction "2_2") (pintype "passive"))
      (node (ref "R3") (pin "2") (pinfunction "2_2") (pintype "passive"))
      (node (ref "U1") (pin "33") (pinfunction "XTAL2_33") (pintype "output"))
      (node (ref "Y1") (pin "2") (pinfunction "OSC2_2") (pintype "passive"))
    )
    (net (code "113") (name "Net-(U2-3V3OUT)") (class "Default")
      (node (ref "C1") (pin "1") (pinfunction "1_1") (pintype "passive"))
      (node (ref "U2") (pin "17") (pinfunction "3V3OUT_17") (pintype "output"))
    )
    (net (code "114") (name "Net-(U2-USBDM)") (class "Default")
      (node (ref "U2") (pin "16") (pinfunction "USBDM_16") (pintype "bidirectional"))
      (node (ref "USB1") (pin "2") (pinfunction "D-_2") (pintype "input"))
    )
    (net (code "115") (name "Net-(U2-USBDP)") (class "Default")
      (node (ref "U2") (pin "15") (pinfunction "USBDP_15") (pintype "bidirectional"))
      (node (ref "USB1") (pin "3") (pinfunction "D+_3") (pintype "input"))
    )
    (net (code "116") (name "Net-(USB1-VBUS)") (class "Default")
      (node (ref "F1") (pin "1") (pinfunction "1_1") (pintype "passive"))
      (node (ref "USB1") (pin "1") (pinfunction "VBUS_1") (pintype "power_in"))
    )
    (net (code "117") (name "VCC") (class "Default")
      (node (ref "C12") (pin "2") (pinfunction "2_2") (pintype "passive"))
      (node (ref "C3") (pin "2") (pinfunction "2_2") (pintype "passive"))
      (node (ref "C5") (pin "2") (pinfunction "2_2") (pintype "passive"))
      (node (ref "C8") (pin "1") (pinfunction "1_1") (pintype "passive"))
      (node (ref "D1") (pin "2") (pinfunction "K_2") (pintype "passive"))
      (node (ref "D2") (pin "2") (pinfunction "K_2") (pintype "passive"))
      (node (ref "L1") (pin "2") (pinfunction "2_2") (pintype "passive"))
      (node (ref "L2") (pin "2") (pinfunction "2_2") (pintype "passive"))
      (node (ref "L3") (pin "2") (pinfunction "2_2") (pintype "passive"))
      (node (ref "M2") (pin "1") (pinfunction "VCC_IN_1") (pintype "power_in"))
      (node (ref "P1") (pin "4") (pinfunction "4_4") (pintype "passive"))
      (node (ref "P1") (pin "7") (pinfunction "7_7") (pintype "passive"))
      (node (ref "P10") (pin "5") (pinfunction "5_5") (pintype "passive"))
      (node (ref "P12") (pin "1") (pinfunction "1_1") (pintype "passive"))
      (node (ref "P13") (pin "1") (pinfunction "1_1") (pintype "passive"))
      (node (ref "P14") (pin "5") (pinfunction "5_5") (pintype "passive"))
      (node (ref "P15") (pin "5") (pinfunction "5_5") (pintype "passive"))
      (node (ref "P16") (pin "1") (pinfunction "1_1") (pintype "passive"))
      (node (ref "P17") (pin "1") (pinfunction "1_1") (pintype "passive"))
      (node (ref "P18") (pin "1") (pinfunction "1_1") (pintype "passive"))
      (node (ref "P19") (pin "5") (pinfunction "5_5") (pintype "passive"))
      (node (ref "P2") (pin "2") (pinfunction "2_2") (pintype "passive"))
      (node (ref "P20") (pin "5") (pinfunction "5_5") (pintype "passive"))
      (node (ref "P22") (pin "9") (pinfunction "9_9") (pintype "passive"))
      (node (ref "P3") (pin "1") (pinfunction "1_1") (pintype "passive"))
      (node (ref "P4") (pin "1") (pinfunction "1_1") (pintype "passive"))
      (node (ref "P5") (pin "5") (pinfunction "5_5") (pintype "passive"))
      (node (ref "P6") (pin "5") (pinfunction "5_5") (pintype "passive"))
      (node (ref "P7") (pin "1") (pinfunction "1_1") (pintype "passive"))
      (node (ref "P8") (pin "1") (pinfunction "1_1") (pintype "passive"))
      (node (ref "P9") (pin "5") (pinfunction "5_5") (pintype "passive"))
      (node (ref "R1") (pin "2") (pinfunction "2_2") (pintype "passive"))
      (node (ref "R2") (pin "2") (pinfunction "2_2") (pintype "passive"))
      (node (ref "R6") (pin "1") (pinfunction "1_1") (pintype "passive"))
      (node (ref "R7") (pin "1") (pinfunction "1_1") (pintype "passive"))
      (node (ref "R8") (pin "1") (pinfunction "1_1") (pintype "passive"))
      (node (ref "R9") (pin "2") (pinfunction "2_2") (pintype "passive"))
      (node (ref "U1") (pin "10") (pinfunction "VCC_10") (pintype "power_in"))
      (node (ref "U1") (pin "31") (pinfunction "VCC_31") (pintype "power_in"))
      (node (ref "U1") (pin "61") (pinfunction "VCC_61") (pintype "power_in"))
      (node (ref "U1") (pin "80") (pinfunction "VCC_80") (pintype "power_in"))
      (node (ref "U2") (pin "20") (pinfunction "VCC_20") (pintype "power_in"))
      (node (ref "U2") (pin "4") (pinfunction "VCCIO_4") (pintype "power_in"))
      (node (ref "U3") (pin "3") (pinfunction "IN_3") (pintype "power_in"))
    )
    (net (code "118") (name "unconnected-(M2-3.3V-Pad2)") (class "Default")
      (node (ref "M2") (pin "2") (pinfunction "3.3V_2") (pintype "power_in"))
    )
    (net (code "119") (name "unconnected-(M2-DRDY-Pad8)") (class "Default")
      (node (ref "M2") (pin "8") (pinfunction "DRDY_8") (pintype "input"))
    )
    (net (code "120") (name "unconnected-(M2-FSYNC-Pad6)") (class "Default")
      (node (ref "M2") (pin "6") (pinfunction "FSYNC_6") (pintype "input"))
    )
    (net (code "121") (name "unconnected-(M2-INTA-Pad7)") (class "Default")
      (node (ref "M2") (pin "7") (pinfunction "INTA_7") (pintype "output"))
    )
    (net (code "122") (name "unconnected-(P1-Pad8)") (class "Default")
      (node (ref "P1") (pin "8") (pinfunction "8_8") (pintype "passive+no_connect"))
    )
    (net (code "123") (name "unconnected-(P2-Pad3)") (class "Default")
      (node (ref "P2") (pin "3") (pinfunction "3_3") (pintype "passive+no_connect"))
    )
    (net (code "124") (name "unconnected-(P5-Pad2)") (class "Default")
      (node (ref "P5") (pin "2") (pinfunction "2_2") (pintype "passive+no_connect"))
    )
    (net (code "125") (name "unconnected-(P6-Pad2)") (class "Default")
      (node (ref "P6") (pin "2") (pinfunction "2_2") (pintype "passive+no_connect"))
    )
    (net (code "126") (name "unconnected-(P9-Pad2)") (class "Default")
      (node (ref "P9") (pin "2") (pinfunction "2_2") (pintype "passive+no_connect"))
    )
    (net (code "127") (name "unconnected-(P10-Pad2)") (class "Default")
      (node (ref "P10") (pin "2") (pinfunction "2_2") (pintype "passive+no_connect"))
    )
    (net (code "128") (name "unconnected-(P14-Pad2)") (class "Default")
      (node (ref "P14") (pin "2") (pinfunction "2_2") (pintype "passive+no_connect"))
    )
    (net (code "129") (name "unconnected-(P15-Pad2)") (class "Default")
      (node (ref "P15") (pin "2") (pinfunction "2_2") (pintype "passive+no_connect"))
    )
    (net (code "130") (name "unconnected-(P19-Pad2)") (class "Default")
      (node (ref "P19") (pin "2") (pinfunction "2_2") (pintype "passive+no_connect"))
    )
    (net (code "131") (name "unconnected-(P20-Pad2)") (class "Default")
      (node (ref "P20") (pin "2") (pinfunction "2_2") (pintype "passive+no_connect"))
    )
    (net (code "132") (name "unconnected-(U2-NC-Pad8)") (class "Default")
      (node (ref "U2") (pin "8") (pinfunction "NC_8") (pintype "passive+no_connect"))
    )
    (net (code "133") (name "unconnected-(U2-NC-Pad24)") (class "Default")
      (node (ref "U2") (pin "24") (pinfunction "NC_24") (pintype "passive+no_connect"))
    )
    (net (code "134") (name "unconnected-(U2-OSCI-Pad27)") (class "Default")
      (node (ref "U2") (pin "27") (pinfunction "OSCI_27") (pintype "input"))
    )
    (net (code "135") (name "unconnected-(U2-OSCO-Pad28)") (class "Default")
      (node (ref "U2") (pin "28") (pinfunction "OSCO_28") (pintype "output"))
    )
    (net (code "136") (name "unconnected-(USB1-SHLD-Pad5)") (class "Default")
      (node (ref "USB1") (pin "5") (pinfunction "SHLD_5") (pintype "passive+no_connect"))
    )
    (net (code "137") (name "unconnected-(USB1-SHLD-Pad6)") (class "Default")
      (node (ref "USB1") (pin "6") (pinfunction "SHLD_6") (pintype "passive+no_connect"))
    )
  )
)
